# doorjamb_rev_a.net
KiCad netlist of a schematic drawn in EAGLE
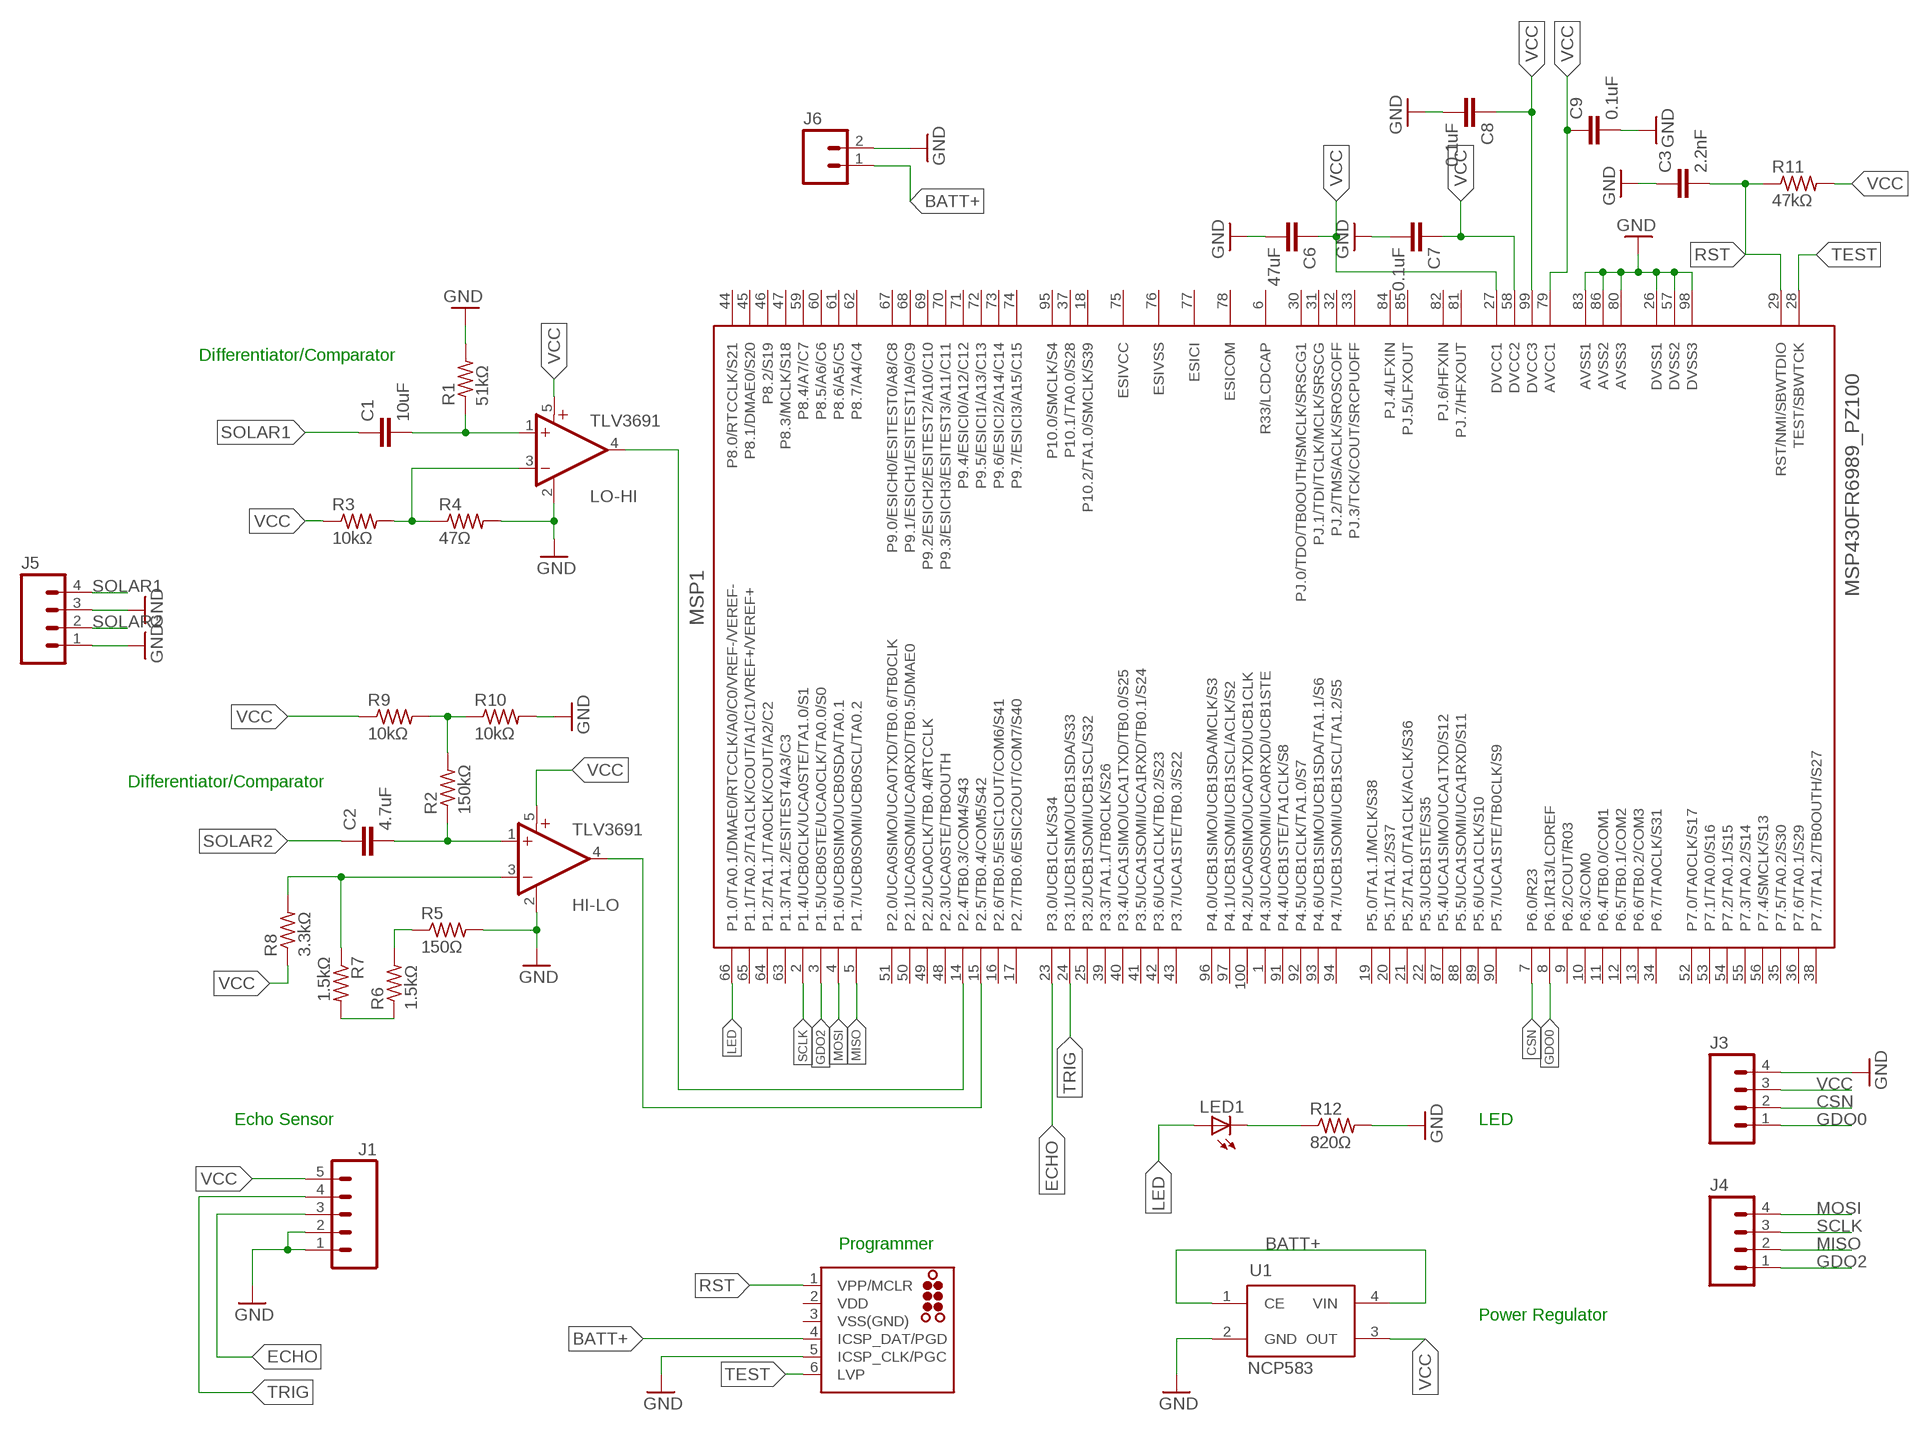
[diagram p0: schematic, sheet 1]

(export (version "E")
  (design (tool "Eeschema 10.0.6"))
  (components
    (comp (ref "C1")
      (value "10uF")
      (footprint "eagle-import:0805")
      (libsource (lib "eagle-import") (part "CAP0805"))
    )
    (comp (ref "C2")
      (value "4.7uF")
      (footprint "eagle-import:0805")
      (libsource (lib "eagle-import") (part "CAP0805"))
    )
    (comp (ref "C3")
      (value "2.2nF")
      (footprint "eagle-import:0805")
      (libsource (lib "eagle-import") (part "CAP0805"))
    )
    (comp (ref "C6")
      (value "47uF")
      (footprint "eagle-import:0805")
      (libsource (lib "eagle-import") (part "CAP0805"))
    )
    (comp (ref "C7")
      (value "0.1uF")
      (footprint "eagle-import:0805")
      (libsource (lib "eagle-import") (part "CAP0805"))
    )
    (comp (ref "C8")
      (value "0.1uF")
      (footprint "eagle-import:0805")
      (libsource (lib "eagle-import") (part "CAP0805"))
    )
    (comp (ref "C9")
      (value "0.1uF")
      (footprint "eagle-import:0805")
      (libsource (lib "eagle-import") (part "CAP0805"))
    )
    (comp (ref "HI-LO")
      (value "TLV3691")
      (footprint "eagle-import:SC70-5")
      (libsource (lib "eagle-import") (part "TLV3691"))
    )
    (comp (ref "J1")
      (value "M05PTH")
      (footprint "eagle-import:1X05")
      (libsource (lib "eagle-import") (part "M05PTH"))
    )
    (comp (ref "J2")
      (value "TC2030-MCP-NL")
      (footprint "eagle-import:TC2030-MCP-NL")
      (libsource (lib "eagle-import") (part "TC2030-MCP-NL"))
    )
    (comp (ref "J3")
      (value "M04PTH")
      (footprint "eagle-import:1X04")
      (libsource (lib "eagle-import") (part "M04PTH"))
    )
    (comp (ref "J4")
      (value "M04PTH")
      (footprint "eagle-import:1X04")
      (libsource (lib "eagle-import") (part "M04PTH"))
    )
    (comp (ref "J5")
      (value "M04PTH")
      (footprint "eagle-import:1X04")
      (libsource (lib "eagle-import") (part "M04PTH"))
    )
    (comp (ref "J6")
      (value "M02PTH")
      (footprint "eagle-import:1X02")
      (libsource (lib "eagle-import") (part "M02PTH"))
    )
    (comp (ref "LED1")
      (value "LEDCHIP-LED0805")
      (footprint "eagle-import:CHIP-LED0805")
      (libsource (lib "eagle-import") (part "LEDCHIP-LED0805"))
    )
    (comp (ref "LO-HI")
      (value "TLV3691")
      (footprint "eagle-import:SC70-5")
      (libsource (lib "eagle-import") (part "TLV3691"))
    )
    (comp (ref "MSP1")
      (value "MSP430FR6989_PZ100")
      (footprint "eagle-import:PZ100")
      (libsource (lib "eagle-import") (part "MSP430FR6989_PZ100"))
    )
    (comp (ref "R1")
      (value "51kΩ")
      (footprint "eagle-import:M0805")
      (libsource (lib "eagle-import") (part "R-US_M0805"))
    )
    (comp (ref "R2")
      (value "150kΩ")
      (footprint "eagle-import:M0805")
      (libsource (lib "eagle-import") (part "R-US_M0805"))
    )
    (comp (ref "R3")
      (value "10kΩ")
      (footprint "eagle-import:M0805")
      (libsource (lib "eagle-import") (part "R-US_M0805"))
    )
    (comp (ref "R4")
      (value "47Ω")
      (footprint "eagle-import:M0805")
      (libsource (lib "eagle-import") (part "R-US_M0805"))
    )
    (comp (ref "R5")
      (value "150Ω")
      (footprint "eagle-import:M0805")
      (libsource (lib "eagle-import") (part "R-US_M0805"))
    )
    (comp (ref "R6")
      (value "1.5kΩ")
      (footprint "eagle-import:M0805")
      (libsource (lib "eagle-import") (part "R-US_M0805"))
    )
    (comp (ref "R7")
      (value "1.5kΩ")
      (footprint "eagle-import:M0805")
      (libsource (lib "eagle-import") (part "R-US_M0805"))
    )
    (comp (ref "R8")
      (value "3.3kΩ")
      (footprint "eagle-import:M0805")
      (libsource (lib "eagle-import") (part "R-US_M0805"))
    )
    (comp (ref "R9")
      (value "10kΩ")
      (footprint "eagle-import:M0805")
      (libsource (lib "eagle-import") (part "R-US_M0805"))
    )
    (comp (ref "R10")
      (value "10kΩ")
      (footprint "eagle-import:M0805")
      (libsource (lib "eagle-import") (part "R-US_M0805"))
    )
    (comp (ref "R11")
      (value "47kΩ")
      (footprint "eagle-import:M0805")
      (libsource (lib "eagle-import") (part "R-US_M0805"))
    )
    (comp (ref "R12")
      (value "820Ω")
      (footprint "eagle-import:M0805")
      (libsource (lib "eagle-import") (part "R-US_M0805"))
    )
    (comp (ref "U1")
      (value "NCP583")
      (footprint "eagle-import:SC82-AB_1PRIMARY")
      (libsource (lib "eagle-import") (part "NCP583"))
    )
  )
  (nets
    (net (code "1") (name "/VDD") (class "Default")
      (node (ref "J2") (pin "2") (pinfunction "VDD_2") (pintype "power_in"))
    )
    (net (code "2") (name "/VSS(GND)") (class "Default")
      (node (ref "J2") (pin "3") (pinfunction "VSS(GND)_3") (pintype "power_in"))
    )
    (net (code "3") (name "BATT+") (class "Default")
      (node (ref "J2") (pin "4") (pinfunction "ICSP_DAT/PGD_4") (pintype "bidirectional"))
      (node (ref "J6") (pin "1") (pinfunction "1_1") (pintype "passive"))
      (node (ref "U1") (pin "1") (pinfunction "CE_1") (pintype "bidirectional"))
      (node (ref "U1") (pin "4") (pinfunction "VIN_4") (pintype "bidirectional"))
    )
    (net (code "4") (name "CSN") (class "Default")
      (node (ref "J3") (pin "2") (pinfunction "2_2") (pintype "passive"))
      (node (ref "MSP1") (pin "7") (pinfunction "P6.0/R23_7") (pintype "bidirectional"))
    )
    (net (code "5") (name "ECHO") (class "Default")
      (node (ref "J1") (pin "3") (pinfunction "3_3") (pintype "passive"))
      (node (ref "MSP1") (pin "23") (pinfunction "P3.0/UCB1CLK/S34_23") (pintype "bidirectional"))
    )
    (net (code "6") (name "GDO0") (class "Default")
      (node (ref "J3") (pin "1") (pinfunction "1_1") (pintype "passive"))
      (node (ref "MSP1") (pin "8") (pinfunction "P6.1/R13/LCDREF_8") (pintype "bidirectional"))
    )
    (net (code "7") (name "GDO2") (class "Default")
      (node (ref "J4") (pin "1") (pinfunction "1_1") (pintype "passive"))
      (node (ref "MSP1") (pin "3") (pinfunction "P1.5/UCB0STE/UCA0CLK/TA0.0/S0_3") (pintype "bidirectional"))
    )
    (net (code "8") (name "GND") (class "Default")
      (node (ref "C3") (pin "1") (pinfunction "1_1") (pintype "passive"))
      (node (ref "C6") (pin "2") (pinfunction "2_2") (pintype "passive"))
      (node (ref "C7") (pin "2") (pinfunction "2_2") (pintype "passive"))
      (node (ref "C8") (pin "2") (pinfunction "2_2") (pintype "passive"))
      (node (ref "C9") (pin "2") (pinfunction "2_2") (pintype "passive"))
      (node (ref "HI-LO") (pin "2") (pinfunction "GND_2") (pintype "power_in"))
      (node (ref "J1") (pin "1") (pinfunction "1_1") (pintype "passive"))
      (node (ref "J1") (pin "2") (pinfunction "2_2") (pintype "passive"))
      (node (ref "J2") (pin "5") (pinfunction "ICSP_CLK/PGC_5") (pintype "output"))
      (node (ref "J3") (pin "4") (pinfunction "4_4") (pintype "passive"))
      (node (ref "J5") (pin "1") (pinfunction "1_1") (pintype "passive"))
      (node (ref "J5") (pin "3") (pinfunction "3_3") (pintype "passive"))
      (node (ref "J6") (pin "2") (pinfunction "2_2") (pintype "passive"))
      (node (ref "LO-HI") (pin "2") (pinfunction "GND_2") (pintype "power_in"))
      (node (ref "MSP1") (pin "26") (pinfunction "DVSS1_26") (pintype "bidirectional"))
      (node (ref "MSP1") (pin "57") (pinfunction "DVSS2_57") (pintype "bidirectional"))
      (node (ref "MSP1") (pin "80") (pinfunction "AVSS3_80") (pintype "bidirectional"))
      (node (ref "MSP1") (pin "83") (pinfunction "AVSS1_83") (pintype "bidirectional"))
      (node (ref "MSP1") (pin "86") (pinfunction "AVSS2_86") (pintype "bidirectional"))
      (node (ref "MSP1") (pin "98") (pinfunction "DVSS3_98") (pintype "bidirectional"))
      (node (ref "R1") (pin "2") (pinfunction "2_2") (pintype "passive"))
      (node (ref "R10") (pin "2") (pinfunction "2_2") (pintype "passive"))
      (node (ref "R12") (pin "2") (pinfunction "2_2") (pintype "passive"))
      (node (ref "R4") (pin "2") (pinfunction "2_2") (pintype "passive"))
      (node (ref "R5") (pin "2") (pinfunction "2_2") (pintype "passive"))
      (node (ref "U1") (pin "2") (pinfunction "GND_2") (pintype "bidirectional"))
    )
    (net (code "9") (name "LED") (class "Default")
      (node (ref "LED1") (pin "A") (pinfunction "A_A") (pintype "passive"))
      (node (ref "MSP1") (pin "66") (pinfunction "P1.0/TA0.1/DMAE0/RTCCLK/A0/C0/VREF-/VEREF-_66") (pintype "bidirectional"))
    )
    (net (code "10") (name "MISO") (class "Default")
      (node (ref "J4") (pin "2") (pinfunction "2_2") (pintype "passive"))
      (node (ref "MSP1") (pin "5") (pinfunction "P1.7/UCB0SOMI/UCB0SCL/TA0.2_5") (pintype "bidirectional"))
    )
    (net (code "11") (name "MOSI") (class "Default")
      (node (ref "J4") (pin "4") (pinfunction "4_4") (pintype "passive"))
      (node (ref "MSP1") (pin "4") (pinfunction "P1.6/UCB0SIMO/UCB0SDA/TA0.1_4") (pintype "bidirectional"))
    )
    (net (code "12") (name "Net-(HI-LO-+IN)") (class "Default")
      (node (ref "C2") (pin "2") (pinfunction "2_2") (pintype "passive"))
      (node (ref "HI-LO") (pin "1") (pinfunction "+IN_1") (pintype "input"))
      (node (ref "R2") (pin "1") (pinfunction "1_1") (pintype "passive"))
    )
    (net (code "13") (name "Net-(HI-LO--IN)") (class "Default")
      (node (ref "HI-LO") (pin "3") (pinfunction "-IN_3") (pintype "input"))
      (node (ref "R7") (pin "1") (pinfunction "1_1") (pintype "passive"))
      (node (ref "R8") (pin "2") (pinfunction "2_2") (pintype "passive"))
    )
    (net (code "14") (name "Net-(HI-LO-OUT)") (class "Default")
      (node (ref "HI-LO") (pin "4") (pinfunction "OUT_4") (pintype "output"))
      (node (ref "MSP1") (pin "15") (pinfunction "P2.5/TB0.4/COM5/S42_15") (pintype "bidirectional"))
    )
    (net (code "15") (name "Net-(LED1-PadC)") (class "Default")
      (node (ref "LED1") (pin "C") (pinfunction "C_C") (pintype "passive"))
      (node (ref "R12") (pin "1") (pinfunction "1_1") (pintype "passive"))
    )
    (net (code "16") (name "Net-(LO-HI-+IN)") (class "Default")
      (node (ref "C1") (pin "2") (pinfunction "2_2") (pintype "passive"))
      (node (ref "LO-HI") (pin "1") (pinfunction "+IN_1") (pintype "input"))
      (node (ref "R1") (pin "1") (pinfunction "1_1") (pintype "passive"))
    )
    (net (code "17") (name "Net-(LO-HI--IN)") (class "Default")
      (node (ref "LO-HI") (pin "3") (pinfunction "-IN_3") (pintype "input"))
      (node (ref "R3") (pin "2") (pinfunction "2_2") (pintype "passive"))
      (node (ref "R4") (pin "1") (pinfunction "1_1") (pintype "passive"))
    )
    (net (code "18") (name "Net-(LO-HI-OUT)") (class "Default")
      (node (ref "LO-HI") (pin "4") (pinfunction "OUT_4") (pintype "output"))
      (node (ref "MSP1") (pin "14") (pinfunction "P2.4/TB0.3/COM4/S43_14") (pintype "bidirectional"))
    )
    (net (code "19") (name "Net-(R5-Pad1)") (class "Default")
      (node (ref "R5") (pin "1") (pinfunction "1_1") (pintype "passive"))
      (node (ref "R6") (pin "2") (pinfunction "2_2") (pintype "passive"))
    )
    (net (code "20") (name "Net-(R6-Pad1)") (class "Default")
      (node (ref "R6") (pin "1") (pinfunction "1_1") (pintype "passive"))
      (node (ref "R7") (pin "2") (pinfunction "2_2") (pintype "passive"))
    )
    (net (code "21") (name "Net-(R10-Pad1)") (class "Default")
      (node (ref "R10") (pin "1") (pinfunction "1_1") (pintype "passive"))
      (node (ref "R2") (pin "2") (pinfunction "2_2") (pintype "passive"))
      (node (ref "R9") (pin "2") (pinfunction "2_2") (pintype "passive"))
    )
    (net (code "22") (name "RST") (class "Default")
      (node (ref "C3") (pin "2") (pinfunction "2_2") (pintype "passive"))
      (node (ref "J2") (pin "1") (pinfunction "VPP/MCLR_1") (pintype "passive"))
      (node (ref "MSP1") (pin "29") (pinfunction "RST/NMI/SBWTDIO_29") (pintype "bidirectional"))
      (node (ref "R11") (pin "1") (pinfunction "1_1") (pintype "passive"))
    )
    (net (code "23") (name "SCLK") (class "Default")
      (node (ref "J4") (pin "3") (pinfunction "3_3") (pintype "passive"))
      (node (ref "MSP1") (pin "2") (pinfunction "P1.4/UCB0CLK/UCA0STE/TA1.0/S1_2") (pintype "bidirectional"))
    )
    (net (code "24") (name "SOLAR1") (class "Default")
      (node (ref "C1") (pin "1") (pinfunction "1_1") (pintype "passive"))
      (node (ref "J5") (pin "4") (pinfunction "4_4") (pintype "passive"))
    )
    (net (code "25") (name "SOLAR2") (class "Default")
      (node (ref "C2") (pin "1") (pinfunction "1_1") (pintype "passive"))
      (node (ref "J5") (pin "2") (pinfunction "2_2") (pintype "passive"))
    )
    (net (code "26") (name "TEST") (class "Default")
      (node (ref "J2") (pin "6") (pinfunction "LVP_6") (pintype "bidirectional"))
      (node (ref "MSP1") (pin "28") (pinfunction "TEST/SBWTCK_28") (pintype "bidirectional"))
    )
    (net (code "27") (name "TRIG") (class "Default")
      (node (ref "J1") (pin "4") (pinfunction "4_4") (pintype "passive"))
      (node (ref "MSP1") (pin "24") (pinfunction "P3.1/UCB1SIMO/UCB1SDA/S33_24") (pintype "bidirectional"))
    )
    (net (code "28") (name "VCC") (class "Default")
      (node (ref "C6") (pin "1") (pinfunction "1_1") (pintype "passive"))
      (node (ref "C7") (pin "1") (pinfunction "1_1") (pintype "passive"))
      (node (ref "C8") (pin "1") (pinfunction "1_1") (pintype "passive"))
      (node (ref "C9") (pin "1") (pinfunction "1_1") (pintype "passive"))
      (node (ref "HI-LO") (pin "5") (pinfunction "V+_5") (pintype "power_in"))
      (node (ref "J1") (pin "5") (pinfunction "5_5") (pintype "passive"))
      (node (ref "J3") (pin "3") (pinfunction "3_3") (pintype "passive"))
      (node (ref "LO-HI") (pin "5") (pinfunction "V+_5") (pintype "power_in"))
      (node (ref "MSP1") (pin "27") (pinfunction "DVCC1_27") (pintype "bidirectional"))
      (node (ref "MSP1") (pin "58") (pinfunction "DVCC2_58") (pintype "bidirectional"))
      (node (ref "MSP1") (pin "79") (pinfunction "AVCC1_79") (pintype "bidirectional"))
      (node (ref "MSP1") (pin "99") (pinfunction "DVCC3_99") (pintype "bidirectional"))
      (node (ref "R11") (pin "2") (pinfunction "2_2") (pintype "passive"))
      (node (ref "R3") (pin "1") (pinfunction "1_1") (pintype "passive"))
      (node (ref "R8") (pin "1") (pinfunction "1_1") (pintype "passive"))
      (node (ref "R9") (pin "1") (pinfunction "1_1") (pintype "passive"))
      (node (ref "U1") (pin "3") (pinfunction "OUT_3") (pintype "bidirectional"))
    )
    (net (code "29") (name "unconnected-(MSP1-ESICI-Pad77)") (class "Default")
      (node (ref "MSP1") (pin "77") (pinfunction "ESICI_77") (pintype "bidirectional"))
    )
    (net (code "30") (name "unconnected-(MSP1-ESICOM-Pad78)") (class "Default")
      (node (ref "MSP1") (pin "78") (pinfunction "ESICOM_78") (pintype "bidirectional"))
    )
    (net (code "31") (name "unconnected-(MSP1-ESIVCC-Pad75)") (class "Default")
      (node (ref "MSP1") (pin "75") (pinfunction "ESIVCC_75") (pintype "bidirectional"))
    )
    (net (code "32") (name "unconnected-(MSP1-ESIVSS-Pad76)") (class "Default")
      (node (ref "MSP1") (pin "76") (pinfunction "ESIVSS_76") (pintype "bidirectional"))
    )
    (net (code "33") (name "unconnected-(MSP1-P1.1{slash}TA0.2{slash}TA1CLK{slash}COUT{slash}A1{slash}C1{slash}VREF+{slash}VEREF+-Pad65)") (class "Default")
      (node (ref "MSP1") (pin "65") (pinfunction "P1.1/TA0.2/TA1CLK/COUT/A1/C1/VREF+/VEREF+_65") (pintype "bidirectional"))
    )
    (net (code "34") (name "unconnected-(MSP1-P1.2{slash}TA1.1{slash}TA0CLK{slash}COUT{slash}A2{slash}C2-Pad64)") (class "Default")
      (node (ref "MSP1") (pin "64") (pinfunction "P1.2/TA1.1/TA0CLK/COUT/A2/C2_64") (pintype "bidirectional"))
    )
    (net (code "35") (name "unconnected-(MSP1-P1.3{slash}TA1.2{slash}ESITEST4{slash}A3{slash}C3-Pad63)") (class "Default")
      (node (ref "MSP1") (pin "63") (pinfunction "P1.3/TA1.2/ESITEST4/A3/C3_63") (pintype "bidirectional"))
    )
    (net (code "36") (name "unconnected-(MSP1-P2.0{slash}UCA0SIMO{slash}UCA0TXD{slash}TB0.6{slash}TB0CLK-Pad51)") (class "Default")
      (node (ref "MSP1") (pin "51") (pinfunction "P2.0/UCA0SIMO/UCA0TXD/TB0.6/TB0CLK_51") (pintype "bidirectional"))
    )
    (net (code "37") (name "unconnected-(MSP1-P2.1{slash}UCA0SOMI{slash}UCA0RXD{slash}TB0.5{slash}DMAE0-Pad50)") (class "Default")
      (node (ref "MSP1") (pin "50") (pinfunction "P2.1/UCA0SOMI/UCA0RXD/TB0.5/DMAE0_50") (pintype "bidirectional"))
    )
    (net (code "38") (name "unconnected-(MSP1-P2.2{slash}UCA0CLK{slash}TB0.4{slash}RTCCLK-Pad49)") (class "Default")
      (node (ref "MSP1") (pin "49") (pinfunction "P2.2/UCA0CLK/TB0.4/RTCCLK_49") (pintype "bidirectional"))
    )
    (net (code "39") (name "unconnected-(MSP1-P2.3{slash}UCA0STE{slash}TB0OUTH-Pad48)") (class "Default")
      (node (ref "MSP1") (pin "48") (pinfunction "P2.3/UCA0STE/TB0OUTH_48") (pintype "bidirectional"))
    )
    (net (code "40") (name "unconnected-(MSP1-P2.6{slash}TB0.5{slash}ESIC1OUT{slash}COM6{slash}S41-Pad16)") (class "Default")
      (node (ref "MSP1") (pin "16") (pinfunction "P2.6/TB0.5/ESIC1OUT/COM6/S41_16") (pintype "bidirectional"))
    )
    (net (code "41") (name "unconnected-(MSP1-P2.7{slash}TB0.6{slash}ESIC2OUT{slash}COM7{slash}S40-Pad17)") (class "Default")
      (node (ref "MSP1") (pin "17") (pinfunction "P2.7/TB0.6/ESIC2OUT/COM7/S40_17") (pintype "bidirectional"))
    )
    (net (code "42") (name "unconnected-(MSP1-P3.2{slash}UCB1SOMI{slash}UCB1SCL{slash}S32-Pad25)") (class "Default")
      (node (ref "MSP1") (pin "25") (pinfunction "P3.2/UCB1SOMI/UCB1SCL/S32_25") (pintype "bidirectional"))
    )
    (net (code "43") (name "unconnected-(MSP1-P3.3{slash}TA1.1{slash}TB0CLK{slash}S26-Pad39)") (class "Default")
      (node (ref "MSP1") (pin "39") (pinfunction "P3.3/TA1.1/TB0CLK/S26_39") (pintype "bidirectional"))
    )
    (net (code "44") (name "unconnected-(MSP1-P3.4{slash}UCA1SIMO{slash}UCA1TXD{slash}TB0.0{slash}S25-Pad40)") (class "Default")
      (node (ref "MSP1") (pin "40") (pinfunction "P3.4/UCA1SIMO/UCA1TXD/TB0.0/S25_40") (pintype "bidirectional"))
    )
    (net (code "45") (name "unconnected-(MSP1-P3.5{slash}UCA1SOMI{slash}UCA1RXD{slash}TB0.1{slash}S24-Pad41)") (class "Default")
      (node (ref "MSP1") (pin "41") (pinfunction "P3.5/UCA1SOMI/UCA1RXD/TB0.1/S24_41") (pintype "bidirectional"))
    )
    (net (code "46") (name "unconnected-(MSP1-P3.6{slash}UCA1CLK{slash}TB0.2{slash}S23-Pad42)") (class "Default")
      (node (ref "MSP1") (pin "42") (pinfunction "P3.6/UCA1CLK/TB0.2/S23_42") (pintype "bidirectional"))
    )
    (net (code "47") (name "unconnected-(MSP1-P3.7{slash}UCA1STE{slash}TB0.3{slash}S22-Pad43)") (class "Default")
      (node (ref "MSP1") (pin "43") (pinfunction "P3.7/UCA1STE/TB0.3/S22_43") (pintype "bidirectional"))
    )
    (net (code "48") (name "unconnected-(MSP1-P4.0{slash}UCB1SIMO{slash}UCB1SDA{slash}MCLK{slash}S3-Pad96)") (class "Default")
      (node (ref "MSP1") (pin "96") (pinfunction "P4.0/UCB1SIMO/UCB1SDA/MCLK/S3_96") (pintype "bidirectional"))
    )
    (net (code "49") (name "unconnected-(MSP1-P4.1{slash}UCB1SOMI{slash}UCB1SCL{slash}ACLK{slash}S2-Pad97)") (class "Default")
      (node (ref "MSP1") (pin "97") (pinfunction "P4.1/UCB1SOMI/UCB1SCL/ACLK/S2_97") (pintype "bidirectional"))
    )
    (net (code "50") (name "unconnected-(MSP1-P4.2{slash}UCA0SIMO{slash}UCA0TXD{slash}UCB1CLK-Pad100)") (class "Default")
      (node (ref "MSP1") (pin "100") (pinfunction "P4.2/UCA0SIMO/UCA0TXD/UCB1CLK_100") (pintype "bidirectional"))
    )
    (net (code "51") (name "unconnected-(MSP1-P4.3{slash}UCA0SOMI{slash}UCA0RXD{slash}UCB1STE-Pad1)") (class "Default")
      (node (ref "MSP1") (pin "1") (pinfunction "P4.3/UCA0SOMI/UCA0RXD/UCB1STE_1") (pintype "bidirectional"))
    )
    (net (code "52") (name "unconnected-(MSP1-P4.4{slash}UCB1STE{slash}TA1CLK{slash}S8-Pad91)") (class "Default")
      (node (ref "MSP1") (pin "91") (pinfunction "P4.4/UCB1STE/TA1CLK/S8_91") (pintype "bidirectional"))
    )
    (net (code "53") (name "unconnected-(MSP1-P4.5{slash}UCB1CLK{slash}TA1.0{slash}S7-Pad92)") (class "Default")
      (node (ref "MSP1") (pin "92") (pinfunction "P4.5/UCB1CLK/TA1.0/S7_92") (pintype "bidirectional"))
    )
    (net (code "54") (name "unconnected-(MSP1-P4.6{slash}UCB1SIMO{slash}UCB1SDA{slash}TA1.1{slash}S6-Pad93)") (class "Default")
      (node (ref "MSP1") (pin "93") (pinfunction "P4.6/UCB1SIMO/UCB1SDA/TA1.1/S6_93") (pintype "bidirectional"))
    )
    (net (code "55") (name "unconnected-(MSP1-P4.7{slash}UCB1SOMI{slash}UCB1SCL{slash}TA1.2{slash}S5-Pad94)") (class "Default")
      (node (ref "MSP1") (pin "94") (pinfunction "P4.7/UCB1SOMI/UCB1SCL/TA1.2/S5_94") (pintype "bidirectional"))
    )
    (net (code "56") (name "unconnected-(MSP1-P5.0{slash}TA1.1{slash}MCLK{slash}S38-Pad19)") (class "Default")
      (node (ref "MSP1") (pin "19") (pinfunction "P5.0/TA1.1/MCLK/S38_19") (pintype "bidirectional"))
    )
    (net (code "57") (name "unconnected-(MSP1-P5.1{slash}TA1.2{slash}S37-Pad20)") (class "Default")
      (node (ref "MSP1") (pin "20") (pinfunction "P5.1/TA1.2/S37_20") (pintype "bidirectional"))
    )
    (net (code "58") (name "unconnected-(MSP1-P5.2{slash}TA1.0{slash}TA1CLK{slash}ACLK{slash}S36-Pad21)") (class "Default")
      (node (ref "MSP1") (pin "21") (pinfunction "P5.2/TA1.0/TA1CLK/ACLK/S36_21") (pintype "bidirectional"))
    )
    (net (code "59") (name "unconnected-(MSP1-P5.3{slash}UCB1STE{slash}S35-Pad22)") (class "Default")
      (node (ref "MSP1") (pin "22") (pinfunction "P5.3/UCB1STE/S35_22") (pintype "bidirectional"))
    )
    (net (code "60") (name "unconnected-(MSP1-P5.4{slash}UCA1SIMO{slash}UCA1TXD{slash}S12-Pad87)") (class "Default")
      (node (ref "MSP1") (pin "87") (pinfunction "P5.4/UCA1SIMO/UCA1TXD/S12_87") (pintype "bidirectional"))
    )
    (net (code "61") (name "unconnected-(MSP1-P5.5{slash}UCA1SOMI{slash}UCA1RXD{slash}S11-Pad88)") (class "Default")
      (node (ref "MSP1") (pin "88") (pinfunction "P5.5/UCA1SOMI/UCA1RXD/S11_88") (pintype "bidirectional"))
    )
    (net (code "62") (name "unconnected-(MSP1-P5.6{slash}UCA1CLK{slash}S10-Pad89)") (class "Default")
      (node (ref "MSP1") (pin "89") (pinfunction "P5.6/UCA1CLK/S10_89") (pintype "bidirectional"))
    )
    (net (code "63") (name "unconnected-(MSP1-P5.7{slash}UCA1STE{slash}TB0CLK{slash}S9-Pad90)") (class "Default")
      (node (ref "MSP1") (pin "90") (pinfunction "P5.7/UCA1STE/TB0CLK/S9_90") (pintype "bidirectional"))
    )
    (net (code "64") (name "unconnected-(MSP1-P6.2{slash}COUT{slash}R03-Pad9)") (class "Default")
      (node (ref "MSP1") (pin "9") (pinfunction "P6.2/COUT/R03_9") (pintype "bidirectional"))
    )
    (net (code "65") (name "unconnected-(MSP1-P6.3{slash}COM0-Pad10)") (class "Default")
      (node (ref "MSP1") (pin "10") (pinfunction "P6.3/COM0_10") (pintype "bidirectional"))
    )
    (net (code "66") (name "unconnected-(MSP1-P6.4{slash}TB0.0{slash}COM1-Pad11)") (class "Default")
      (node (ref "MSP1") (pin "11") (pinfunction "P6.4/TB0.0/COM1_11") (pintype "bidirectional"))
    )
    (net (code "67") (name "unconnected-(MSP1-P6.5{slash}TB0.1{slash}COM2-Pad12)") (class "Default")
      (node (ref "MSP1") (pin "12") (pinfunction "P6.5/TB0.1/COM2_12") (pintype "bidirectional"))
    )
    (net (code "68") (name "unconnected-(MSP1-P6.6{slash}TB0.2{slash}COM3-Pad13)") (class "Default")
      (node (ref "MSP1") (pin "13") (pinfunction "P6.6/TB0.2/COM3_13") (pintype "bidirectional"))
    )
    (net (code "69") (name "unconnected-(MSP1-P6.7{slash}TA0CLK{slash}S31-Pad34)") (class "Default")
      (node (ref "MSP1") (pin "34") (pinfunction "P6.7/TA0CLK/S31_34") (pintype "bidirectional"))
    )
    (net (code "70") (name "unconnected-(MSP1-P7.0{slash}TA0CLK{slash}S17-Pad52)") (class "Default")
      (node (ref "MSP1") (pin "52") (pinfunction "P7.0/TA0CLK/S17_52") (pintype "bidirectional"))
    )
    (net (code "71") (name "unconnected-(MSP1-P7.1{slash}TA0.0{slash}S16-Pad53)") (class "Default")
      (node (ref "MSP1") (pin "53") (pinfunction "P7.1/TA0.0/S16_53") (pintype "bidirectional"))
    )
    (net (code "72") (name "unconnected-(MSP1-P7.2{slash}TA0.1{slash}S15-Pad54)") (class "Default")
      (node (ref "MSP1") (pin "54") (pinfunction "P7.2/TA0.1/S15_54") (pintype "bidirectional"))
    )
    (net (code "73") (name "unconnected-(MSP1-P7.3{slash}TA0.2{slash}S14-Pad55)") (class "Default")
      (node (ref "MSP1") (pin "55") (pinfunction "P7.3/TA0.2/S14_55") (pintype "bidirectional"))
    )
    (net (code "74") (name "unconnected-(MSP1-P7.4{slash}SMCLK{slash}S13-Pad56)") (class "Default")
      (node (ref "MSP1") (pin "56") (pinfunction "P7.4/SMCLK/S13_56") (pintype "bidirectional"))
    )
    (net (code "75") (name "unconnected-(MSP1-P7.5{slash}TA0.2{slash}S30-Pad35)") (class "Default")
      (node (ref "MSP1") (pin "35") (pinfunction "P7.5/TA0.2/S30_35") (pintype "bidirectional"))
    )
    (net (code "76") (name "unconnected-(MSP1-P7.6{slash}TA0.1{slash}S29-Pad36)") (class "Default")
      (node (ref "MSP1") (pin "36") (pinfunction "P7.6/TA0.1/S29_36") (pintype "bidirectional"))
    )
    (net (code "77") (name "unconnected-(MSP1-P7.7{slash}TA1.2{slash}TB0OUTH{slash}S27-Pad38)") (class "Default")
      (node (ref "MSP1") (pin "38") (pinfunction "P7.7/TA1.2/TB0OUTH/S27_38") (pintype "bidirectional"))
    )
    (net (code "78") (name "unconnected-(MSP1-P8.0{slash}RTCCLK{slash}S21-Pad44)") (class "Default")
      (node (ref "MSP1") (pin "44") (pinfunction "P8.0/RTCCLK/S21_44") (pintype "bidirectional"))
    )
    (net (code "79") (name "unconnected-(MSP1-P8.1{slash}DMAE0{slash}S20-Pad45)") (class "Default")
      (node (ref "MSP1") (pin "45") (pinfunction "P8.1/DMAE0/S20_45") (pintype "bidirectional"))
    )
    (net (code "80") (name "unconnected-(MSP1-P8.2{slash}S19-Pad46)") (class "Default")
      (node (ref "MSP1") (pin "46") (pinfunction "P8.2/S19_46") (pintype "bidirectional"))
    )
    (net (code "81") (name "unconnected-(MSP1-P8.3{slash}MCLK{slash}S18-Pad47)") (class "Default")
      (node (ref "MSP1") (pin "47") (pinfunction "P8.3/MCLK/S18_47") (pintype "bidirectional"))
    )
    (net (code "82") (name "unconnected-(MSP1-P8.4{slash}A7{slash}C7-Pad59)") (class "Default")
      (node (ref "MSP1") (pin "59") (pinfunction "P8.4/A7/C7_59") (pintype "bidirectional"))
    )
    (net (code "83") (name "unconnected-(MSP1-P8.5{slash}A6{slash}C6-Pad60)") (class "Default")
      (node (ref "MSP1") (pin "60") (pinfunction "P8.5/A6/C6_60") (pintype "bidirectional"))
    )
    (net (code "84") (name "unconnected-(MSP1-P8.6{slash}A5{slash}C5-Pad61)") (class "Default")
      (node (ref "MSP1") (pin "61") (pinfunction "P8.6/A5/C5_61") (pintype "bidirectional"))
    )
    (net (code "85") (name "unconnected-(MSP1-P8.7{slash}A4{slash}C4-Pad62)") (class "Default")
      (node (ref "MSP1") (pin "62") (pinfunction "P8.7/A4/C4_62") (pintype "bidirectional"))
    )
    (net (code "86") (name "unconnected-(MSP1-P9.0{slash}ESICH0{slash}ESITEST0{slash}A8{slash}C8-Pad67)") (class "Default")
      (node (ref "MSP1") (pin "67") (pinfunction "P9.0/ESICH0/ESITEST0/A8/C8_67") (pintype "bidirectional"))
    )
    (net (code "87") (name "unconnected-(MSP1-P9.1{slash}ESICH1{slash}ESITEST1{slash}A9{slash}C9-Pad68)") (class "Default")
      (node (ref "MSP1") (pin "68") (pinfunction "P9.1/ESICH1/ESITEST1/A9/C9_68") (pintype "bidirectional"))
    )
    (net (code "88") (name "unconnected-(MSP1-P9.2{slash}ESICH2{slash}ESITEST2{slash}A10{slash}C10-Pad69)") (class "Default")
      (node (ref "MSP1") (pin "69") (pinfunction "P9.2/ESICH2/ESITEST2/A10/C10_69") (pintype "bidirectional"))
    )
    (net (code "89") (name "unconnected-(MSP1-P9.3{slash}ESICH3{slash}ESITEST3{slash}A11{slash}C11-Pad70)") (class "Default")
      (node (ref "MSP1") (pin "70") (pinfunction "P9.3/ESICH3/ESITEST3/A11/C11_70") (pintype "bidirectional"))
    )
    (net (code "90") (name "unconnected-(MSP1-P9.4{slash}ESICI0{slash}A12{slash}C12-Pad71)") (class "Default")
      (node (ref "MSP1") (pin "71") (pinfunction "P9.4/ESICI0/A12/C12_71") (pintype "bidirectional"))
    )
    (net (code "91") (name "unconnected-(MSP1-P9.5{slash}ESICI1{slash}A13{slash}C13-Pad72)") (class "Default")
      (node (ref "MSP1") (pin "72") (pinfunction "P9.5/ESICI1/A13/C13_72") (pintype "bidirectional"))
    )
    (net (code "92") (name "unconnected-(MSP1-P9.6{slash}ESICI2{slash}A14{slash}C14-Pad73)") (class "Default")
      (node (ref "MSP1") (pin "73") (pinfunction "P9.6/ESICI2/A14/C14_73") (pintype "bidirectional"))
    )
    (net (code "93") (name "unconnected-(MSP1-P9.7{slash}ESICI3{slash}A15{slash}C15-Pad74)") (class "Default")
      (node (ref "MSP1") (pin "74") (pinfunction "P9.7/ESICI3/A15/C15_74") (pintype "bidirectional"))
    )
    (net (code "94") (name "unconnected-(MSP1-P10.0{slash}SMCLK{slash}S4-Pad95)") (class "Default")
      (node (ref "MSP1") (pin "95") (pinfunction "P10.0/SMCLK/S4_95") (pintype "bidirectional"))
    )
    (net (code "95") (name "unconnected-(MSP1-P10.1{slash}TA0.0{slash}S28-Pad37)") (class "Default")
      (node (ref "MSP1") (pin "37") (pinfunction "P10.1/TA0.0/S28_37") (pintype "bidirectional"))
    )
    (net (code "96") (name "unconnected-(MSP1-P10.2{slash}TA1.0{slash}SMCLK{slash}S39-Pad18)") (class "Default")
      (node (ref "MSP1") (pin "18") (pinfunction "P10.2/TA1.0/SMCLK/S39_18") (pintype "bidirectional"))
    )
    (net (code "97") (name "unconnected-(MSP1-PJ.0{slash}TDO{slash}TB0OUTH{slash}SMCLK{slash}SRSCG1-Pad30)") (class "Default")
      (node (ref "MSP1") (pin "30") (pinfunction "PJ.0/TDO/TB0OUTH/SMCLK/SRSCG1_30") (pintype "bidirectional"))
    )
    (net (code "98") (name "unconnected-(MSP1-PJ.1{slash}TDI{slash}TCLK{slash}MCLK{slash}SRSCG-Pad31)") (class "Default")
      (node (ref "MSP1") (pin "31") (pinfunction "PJ.1/TDI/TCLK/MCLK/SRSCG_31") (pintype "bidirectional"))
    )
    (net (code "99") (name "unconnected-(MSP1-PJ.2{slash}TMS{slash}ACLK{slash}SROSCOFF-Pad32)") (class "Default")
      (node (ref "MSP1") (pin "32") (pinfunction "PJ.2/TMS/ACLK/SROSCOFF_32") (pintype "bidirectional"))
    )
    (net (code "100") (name "unconnected-(MSP1-PJ.3{slash}TCK{slash}COUT{slash}SRCPUOFF-Pad33)") (class "Default")
      (node (ref "MSP1") (pin "33") (pinfunction "PJ.3/TCK/COUT/SRCPUOFF_33") (pintype "bidirectional"))
    )
    (net (code "101") (name "unconnected-(MSP1-PJ.4{slash}LFXIN-Pad84)") (class "Default")
      (node (ref "MSP1") (pin "84") (pinfunction "PJ.4/LFXIN_84") (pintype "bidirectional"))
    )
    (net (code "102") (name "unconnected-(MSP1-PJ.5{slash}LFXOUT-Pad85)") (class "Default")
      (node (ref "MSP1") (pin "85") (pinfunction "PJ.5/LFXOUT_85") (pintype "bidirectional"))
    )
    (net (code "103") (name "unconnected-(MSP1-PJ.6{slash}HFXIN-Pad82)") (class "Default")
      (node (ref "MSP1") (pin "82") (pinfunction "PJ.6/HFXIN_82") (pintype "bidirectional"))
    )
    (net (code "104") (name "unconnected-(MSP1-PJ.7{slash}HFXOUT-Pad81)") (class "Default")
      (node (ref "MSP1") (pin "81") (pinfunction "PJ.7/HFXOUT_81") (pintype "bidirectional"))
    )
    (net (code "105") (name "unconnected-(MSP1-R33{slash}LCDCAP-Pad6)") (class "Default")
      (node (ref "MSP1") (pin "6") (pinfunction "R33/LCDCAP_6") (pintype "bidirectional"))
    )
  )
)
